# directly_driven_md.net
KiCad netlist of a schematic drawn in EAGLE
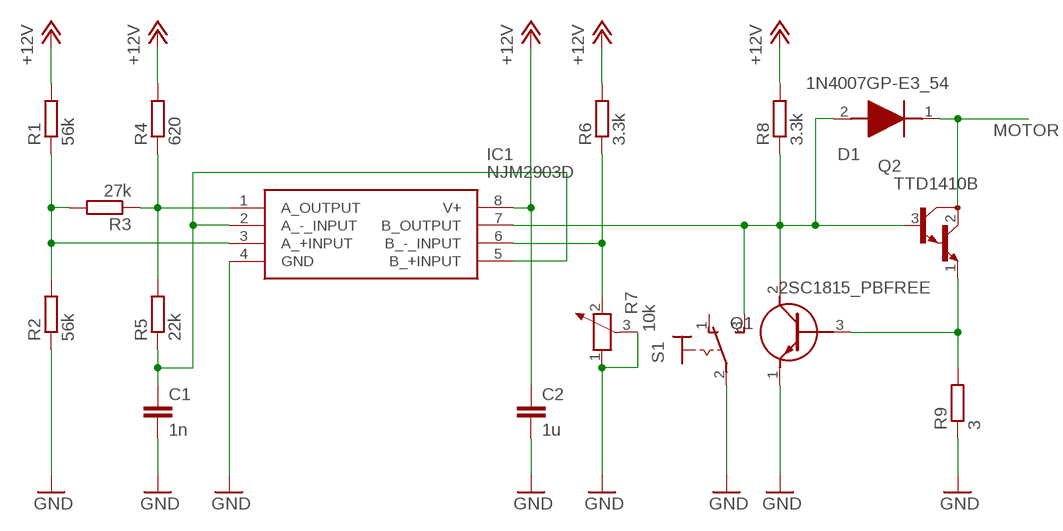
[diagram p0: schematic, sheet 1]
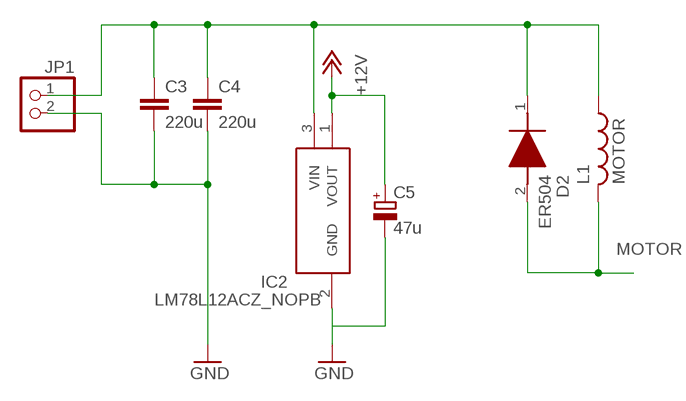
[diagram p1: schematic, sheet 2]

(export (version "E")
  (design (tool "Eeschema 10.0.6"))
  (components
    (comp (ref "C3")
      (value "220u")
      (footprint "eagle-import:C025-025X050")
      (libsource (lib "eagle-import") (part "C-EU025-025X050"))
    )
    (comp (ref "C4")
      (value "220u")
      (footprint "eagle-import:C025-025X050")
      (libsource (lib "eagle-import") (part "C-EU025-025X050"))
    )
    (comp (ref "C5")
      (value "47u")
      (footprint "eagle-import:E2,5-6E")
      (libsource (lib "eagle-import") (part "CPOL-EUE2,5-6E"))
    )
    (comp (ref "D2")
      (value "ER504")
      (footprint "eagle-import:DIOAD2855W130L835D505")
      (libsource (lib "eagle-import") (part "ER504"))
    )
    (comp (ref "IC2")
      (value "LM78L12ACZ_NOPB")
      (footprint "eagle-import:LP0003A")
      (fields
        (field (name "ARROW_PART_NUMBER") "LM78L12ACZ/NOPB")
        (field (name "MOUSER_PART_NUMBER") "926-LM78L12ACZ/NOPB")
      )
      (libsource (lib "eagle-import") (part "LM78L12ACZ_NOPB"))
    )
    (comp (ref "JP1")
      (value "PINHD-1X2")
      (footprint "eagle-import:1X02")
      (libsource (lib "eagle-import") (part "PINHD-1X2"))
    )
    (comp (ref "L1")
      (value "MOTOR")
      (footprint "eagle-import:0207_15")
      (libsource (lib "eagle-import") (part "L-US0207/15"))
    )
    (comp (ref "C1")
      (value "1n")
      (footprint "eagle-import:C025-025X050")
      (libsource (lib "eagle-import") (part "C-EU025-025X050"))
    )
    (comp (ref "C2")
      (value "1u")
      (footprint "eagle-import:C025-025X050")
      (libsource (lib "eagle-import") (part "C-EU025-025X050"))
    )
    (comp (ref "D1")
      (value "1N4007GP-E3_54")
      (footprint "eagle-import:DIOAD1405W86L465D235")
      (fields
        (field (name "ARROW_PART_NUMBER") "1N4007GP-E3/54")
        (field (name "MOUSER_PART_NUMBER") "625-1N4007GP-E3/54")
      )
      (libsource (lib "eagle-import") (part "1N4007GP-E3_54"))
    )
    (comp (ref "IC1")
      (value "NJM2903D")
      (footprint "eagle-import:DIP762W56P254L880H425Q8N")
      (fields (field (name "MOUSER_PART_NUMBER") "513-NJM2903D"))
      (libsource (lib "eagle-import") (part "NJM2903D"))
    )
    (comp (ref "Q1")
      (value "2SC1815_PBFREE")
      (footprint "eagle-import:2SC1815PBFREE")
      (fields
        (field (name "ARROW_PART_NUMBER") "2SC1815 PBFREE")
        (field (name "MOUSER_PART_NUMBER") "610-2SC1815")
      )
      (libsource (lib "eagle-import") (part "2SC1815_PBFREE"))
    )
    (comp (ref "Q2")
      (value "TTD1410B")
      (footprint "eagle-import:TO220AV")
      (libsource (lib "eagle-import") (part "TTD1410B"))
    )
    (comp (ref "R1")
      (value "56k")
      (footprint "eagle-import:0207_10")
      (libsource (lib "eagle-import") (part "R-EU_0207/10"))
    )
    (comp (ref "R2")
      (value "56k")
      (footprint "eagle-import:0207_10")
      (libsource (lib "eagle-import") (part "R-EU_0207/10"))
    )
    (comp (ref "R3")
      (value "27k")
      (footprint "eagle-import:0207_10")
      (libsource (lib "eagle-import") (part "R-EU_0207/10"))
    )
    (comp (ref "R4")
      (value "620")
      (footprint "eagle-import:0207_10")
      (libsource (lib "eagle-import") (part "R-EU_0207/10"))
    )
    (comp (ref "R5")
      (value "22k")
      (footprint "eagle-import:0207_10")
      (libsource (lib "eagle-import") (part "R-EU_0207/10"))
    )
    (comp (ref "R6")
      (value "3.3k")
      (footprint "eagle-import:0207_10")
      (libsource (lib "eagle-import") (part "R-EU_0207/10"))
    )
    (comp (ref "R7")
      (value "10k")
      (footprint "eagle-import:PT-10")
      (libsource (lib "eagle-import") (part "POTENTIOMETER_PT-10"))
    )
    (comp (ref "R8")
      (value "3.3k")
      (footprint "eagle-import:0204_7")
      (libsource (lib "eagle-import") (part "R-EU_0204/7"))
    )
    (comp (ref "R9")
      (value "3")
      (footprint "eagle-import:0204_7")
      (libsource (lib "eagle-import") (part "R-EU_0204/7"))
    )
    (comp (ref "S1")
      (value "320-916")
      (footprint "eagle-import:320-916")
      (libsource (lib "eagle-import") (part "320-916"))
    )
  )
  (nets
    (net (code "1") (name "+12V") (class "Default")
      (node (ref "C2") (pin "1") (pinfunction "1_1") (pintype "passive"))
      (node (ref "C5") (pin "+") (pinfunction "+_+") (pintype "passive"))
      (node (ref "IC1") (pin "8") (pinfunction "V+_8") (pintype "bidirectional"))
      (node (ref "IC2") (pin "1") (pinfunction "VOUT_1") (pintype "bidirectional"))
      (node (ref "R1") (pin "2") (pinfunction "2_2") (pintype "passive"))
      (node (ref "R4") (pin "2") (pinfunction "2_2") (pintype "passive"))
      (node (ref "R6") (pin "2") (pinfunction "2_2") (pintype "passive"))
      (node (ref "R8") (pin "2") (pinfunction "2_2") (pintype "passive"))
    )
    (net (code "2") (name "GND") (class "Default")
      (node (ref "C1") (pin "2") (pinfunction "2_2") (pintype "passive"))
      (node (ref "C2") (pin "2") (pinfunction "2_2") (pintype "passive"))
      (node (ref "C3") (pin "2") (pinfunction "2_2") (pintype "passive"))
      (node (ref "C4") (pin "2") (pinfunction "2_2") (pintype "passive"))
      (node (ref "IC1") (pin "4") (pinfunction "GND_4") (pintype "bidirectional"))
      (node (ref "IC2") (pin "2") (pinfunction "GND_2") (pintype "bidirectional"))
      (node (ref "JP1") (pin "2") (pinfunction "2_2") (pintype "passive"))
      (node (ref "Q1") (pin "1") (pinfunction "E_1") (pintype "bidirectional"))
      (node (ref "R2") (pin "1") (pinfunction "1_1") (pintype "passive"))
      (node (ref "R7") (pin "1") (pinfunction "1_1") (pintype "passive"))
      (node (ref "R7") (pin "3") (pinfunction "3_3") (pintype "passive"))
      (node (ref "R9") (pin "1") (pinfunction "1_1") (pintype "passive"))
      (node (ref "S1") (pin "2") (pinfunction "P_2") (pintype "passive"))
    )
    (net (code "3") (name "MOTOR") (class "Default")
      (node (ref "D1") (pin "1") (pinfunction "K_1") (pintype "bidirectional"))
      (node (ref "D2") (pin "2") (pinfunction "A_2") (pintype "bidirectional"))
      (node (ref "L1") (pin "2") (pinfunction "2_2") (pintype "passive"))
      (node (ref "Q2") (pin "2") (pinfunction "C_2") (pintype "passive"))
    )
    (net (code "4") (name "Net-(D1-A)") (class "Default")
      (node (ref "D1") (pin "2") (pinfunction "A_2") (pintype "bidirectional"))
      (node (ref "IC1") (pin "7") (pinfunction "B_OUTPUT_7") (pintype "bidirectional"))
      (node (ref "Q1") (pin "2") (pinfunction "C_2") (pintype "bidirectional"))
      (node (ref "Q2") (pin "3") (pinfunction "B_3") (pintype "passive"))
      (node (ref "R8") (pin "1") (pinfunction "1_1") (pintype "passive"))
      (node (ref "S1") (pin "3") (pinfunction "S_3") (pintype "passive"))
    )
    (net (code "5") (name "Net-(D2-K)") (class "Default")
      (node (ref "C3") (pin "1") (pinfunction "1_1") (pintype "passive"))
      (node (ref "C4") (pin "1") (pinfunction "1_1") (pintype "passive"))
      (node (ref "D2") (pin "1") (pinfunction "K_1") (pintype "bidirectional"))
      (node (ref "IC2") (pin "3") (pinfunction "VIN_3") (pintype "bidirectional"))
      (node (ref "JP1") (pin "1") (pinfunction "1_1") (pintype "passive"))
      (node (ref "L1") (pin "1") (pinfunction "1_1") (pintype "passive"))
    )
    (net (code "6") (name "Net-(IC1-A_+INPUT)") (class "Default")
      (node (ref "IC1") (pin "3") (pinfunction "A_+INPUT_3") (pintype "bidirectional"))
      (node (ref "R1") (pin "1") (pinfunction "1_1") (pintype "passive"))
      (node (ref "R2") (pin "2") (pinfunction "2_2") (pintype "passive"))
      (node (ref "R3") (pin "2") (pinfunction "2_2") (pintype "passive"))
    )
    (net (code "7") (name "Net-(IC1-A_-_INPUT)") (class "Default")
      (node (ref "C1") (pin "1") (pinfunction "1_1") (pintype "passive"))
      (node (ref "IC1") (pin "2") (pinfunction "A_-_INPUT_2") (pintype "bidirectional"))
      (node (ref "IC1") (pin "5") (pinfunction "B_+INPUT_5") (pintype "bidirectional"))
      (node (ref "R5") (pin "1") (pinfunction "1_1") (pintype "passive"))
    )
    (net (code "8") (name "Net-(IC1-A_OUTPUT)") (class "Default")
      (node (ref "IC1") (pin "1") (pinfunction "A_OUTPUT_1") (pintype "bidirectional"))
      (node (ref "R3") (pin "1") (pinfunction "1_1") (pintype "passive"))
      (node (ref "R4") (pin "1") (pinfunction "1_1") (pintype "passive"))
      (node (ref "R5") (pin "2") (pinfunction "2_2") (pintype "passive"))
    )
    (net (code "9") (name "Net-(IC1-B_-_INPUT)") (class "Default")
      (node (ref "IC1") (pin "6") (pinfunction "B_-_INPUT_6") (pintype "bidirectional"))
      (node (ref "R6") (pin "1") (pinfunction "1_1") (pintype "passive"))
      (node (ref "R7") (pin "2") (pinfunction "2_2") (pintype "passive"))
    )
    (net (code "10") (name "Net-(Q1-B)") (class "Default")
      (node (ref "Q1") (pin "3") (pinfunction "B_3") (pintype "bidirectional"))
      (node (ref "Q2") (pin "1") (pinfunction "E_1") (pintype "passive"))
      (node (ref "R9") (pin "2") (pinfunction "2_2") (pintype "passive"))
    )
    (net (code "11") (name "unconnected-(C5-Pad-)") (class "Default")
      (node (ref "C5") (pin "-") (pinfunction "-_-") (pintype "passive"))
    )
    (net (code "12") (name "unconnected-(S1-O-Pad1)") (class "Default")
      (node (ref "S1") (pin "1") (pinfunction "O_1") (pintype "passive"))
    )
  )
)
